# PING2_PCB.net
KiCad netlist of a schematic drawn in Altium Designer
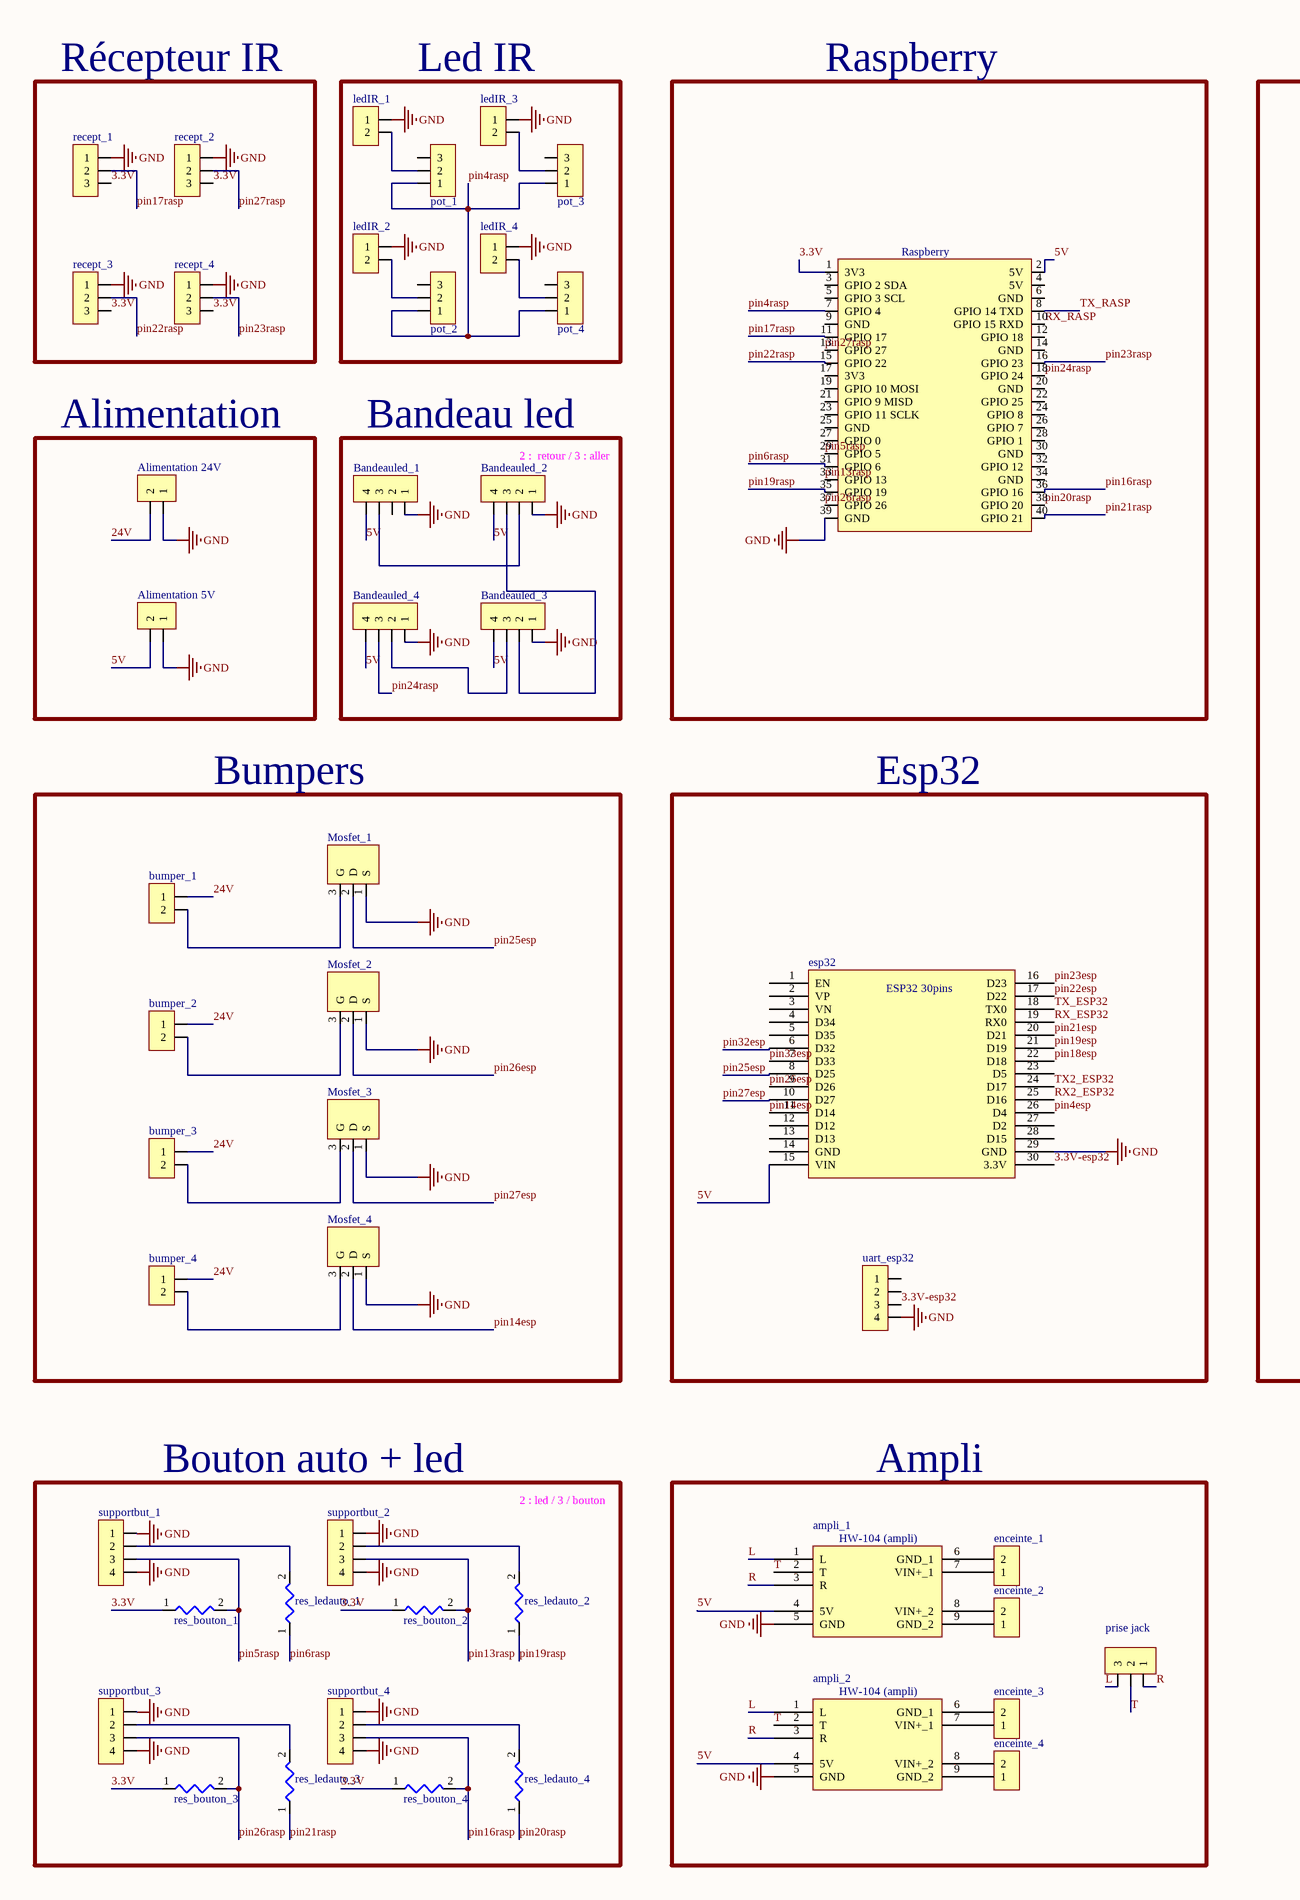
[diagram p0: PING2_PCB.SchDoc, left]
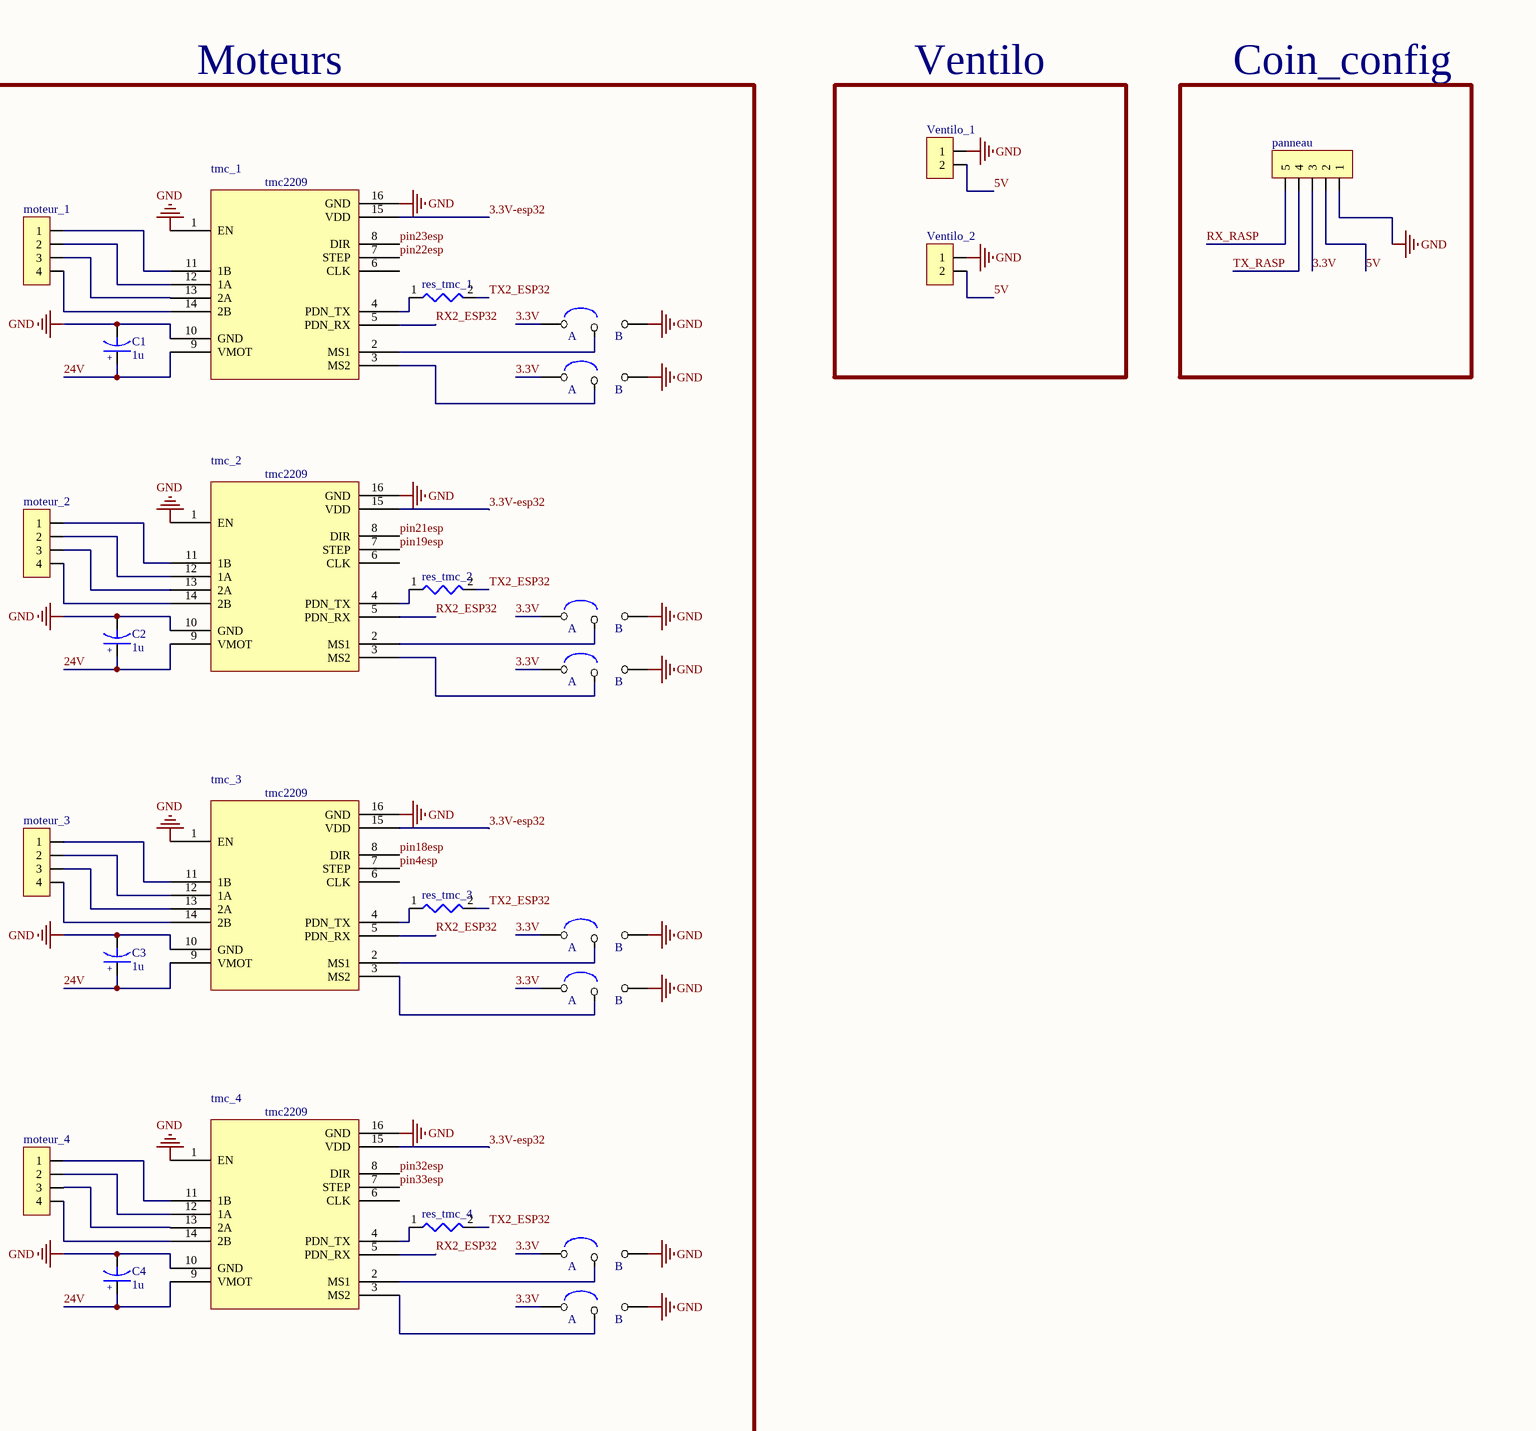
[diagram p1: PING2_PCB.SchDoc, right]

(export (version "E")
  (design (tool "Eeschema 10.0.6"))
  (components
    (comp (ref "Alimentation 5V")
      (value "Header_2")
      (footprint "Header_2")
      (libsource (lib "") (part "Header_2_2"))
    )
    (comp (ref "Alimentation 24V")
      (value "Header_2")
      (footprint "Header_2")
      (libsource (lib "") (part "Header_2_2"))
    )
    (comp (ref "ampli_1")
      (value "HW-104 (ampli)")
      (footprint "HW-104 (ampli)")
      (libsource (lib "Simon_library") (part "HW-104 (ampli)"))
    )
    (comp (ref "ampli_2")
      (value "HW-104 (ampli)")
      (footprint "HW-104 (ampli)")
      (libsource (lib "Simon_library") (part "HW-104 (ampli)"))
    )
    (comp (ref "Bandeauled_1")
      (value "Header_4")
      (footprint "Header_4")
      (libsource (lib "Simon_library") (part "Header_4"))
    )
    (comp (ref "Bandeauled_2")
      (value "Header_4")
      (footprint "Header_4")
      (libsource (lib "Simon_library") (part "Header_4"))
    )
    (comp (ref "Bandeauled_3")
      (value "Header_4")
      (footprint "Header_4")
      (libsource (lib "Simon_library") (part "Header_4"))
    )
    (comp (ref "Bandeauled_4")
      (value "Header_4")
      (footprint "Header_4")
      (libsource (lib "Simon_library") (part "Header_4"))
    )
    (comp (ref "bumper_1")
      (value "Header_2")
      (footprint "Header_2")
      (libsource (lib "Simon_library") (part "Header_2"))
    )
    (comp (ref "bumper_2")
      (value "Header_2")
      (footprint "Header_2")
      (libsource (lib "Simon_library") (part "Header_2"))
    )
    (comp (ref "bumper_3")
      (value "Header_2")
      (footprint "Header_2")
      (libsource (lib "Simon_library") (part "Header_2"))
    )
    (comp (ref "bumper_4")
      (value "Header_2")
      (footprint "Header_2")
      (libsource (lib "Simon_library") (part "Header_2"))
    )
    (comp (ref "C1")
      (value "1u")
      (footprint "RB.2/.4")
      (description "capacité polarisée")
      (fields (field (name "Comment") "CAP_POL"))
      (libsource (lib "ISEN_basics_19052021") (part "CAP_POL"))
    )
    (comp (ref "C2")
      (value "1u")
      (footprint "RB.2/.4")
      (description "capacité polarisée")
      (fields (field (name "Comment") "CAP_POL"))
      (libsource (lib "ISEN_basics_19052021") (part "CAP_POL"))
    )
    (comp (ref "C3")
      (value "1u")
      (footprint "RB.2/.4")
      (description "capacité polarisée")
      (fields (field (name "Comment") "CAP_POL"))
      (libsource (lib "ISEN_basics_19052021") (part "CAP_POL"))
    )
    (comp (ref "C4")
      (value "1u")
      (footprint "RB.2/.4")
      (description "capacité polarisée")
      (fields (field (name "Comment") "CAP_POL"))
      (libsource (lib "ISEN_basics_19052021") (part "CAP_POL"))
    )
    (comp (ref "enceinte_1")
      (value "Header_2")
      (footprint "Header_2")
      (libsource (lib "") (part "Header_2_1"))
    )
    (comp (ref "enceinte_2")
      (value "Header_2")
      (footprint "Header_2")
      (libsource (lib "") (part "Header_2_1"))
    )
    (comp (ref "enceinte_3")
      (value "Header_2")
      (footprint "Header_2")
      (libsource (lib "") (part "Header_2_1"))
    )
    (comp (ref "enceinte_4")
      (value "Header_2")
      (footprint "Header_2")
      (libsource (lib "") (part "Header_2_1"))
    )
    (comp (ref "esp32")
      (value "esp32-30pins")
      (footprint "esp32-30pins")
      (libsource (lib "Simon_library") (part "esp32-30pins"))
    )
    (comp (ref "JMP11")
      (value "JUMPER3")
      (footprint "JMP3-100")
      (description "cavalier 2 positions")
      (libsource (lib "ISEN_basics_19052021") (part "JUMPER3"))
    )
    (comp (ref "JMP12")
      (value "JUMPER3")
      (footprint "JMP3-100")
      (description "cavalier 2 positions")
      (libsource (lib "ISEN_basics_19052021") (part "JUMPER3"))
    )
    (comp (ref "JMP21")
      (value "JUMPER3")
      (footprint "JMP3-100")
      (description "cavalier 2 positions")
      (libsource (lib "ISEN_basics_19052021") (part "JUMPER3"))
    )
    (comp (ref "JMP22")
      (value "JUMPER3")
      (footprint "JMP3-100")
      (description "cavalier 2 positions")
      (libsource (lib "ISEN_basics_19052021") (part "JUMPER3"))
    )
    (comp (ref "JMP31")
      (value "JUMPER3")
      (footprint "JMP3-100")
      (description "cavalier 2 positions")
      (libsource (lib "ISEN_basics_19052021") (part "JUMPER3"))
    )
    (comp (ref "JMP32")
      (value "JUMPER3")
      (footprint "JMP3-100")
      (description "cavalier 2 positions")
      (libsource (lib "ISEN_basics_19052021") (part "JUMPER3"))
    )
    (comp (ref "JMP41")
      (value "JUMPER3")
      (footprint "JMP3-100")
      (description "cavalier 2 positions")
      (libsource (lib "ISEN_basics_19052021") (part "JUMPER3"))
    )
    (comp (ref "JMP42")
      (value "JUMPER3")
      (footprint "JMP3-100")
      (description "cavalier 2 positions")
      (libsource (lib "ISEN_basics_19052021") (part "JUMPER3"))
    )
    (comp (ref "ledIR_1")
      (value "Header_2")
      (footprint "Header_2")
      (libsource (lib "Simon_library") (part "Header_2"))
    )
    (comp (ref "ledIR_2")
      (value "Header_2")
      (footprint "Header_2")
      (libsource (lib "Simon_library") (part "Header_2"))
    )
    (comp (ref "ledIR_3")
      (value "Header_2")
      (footprint "Header_2")
      (libsource (lib "Simon_library") (part "Header_2"))
    )
    (comp (ref "ledIR_4")
      (value "Header_2")
      (footprint "Header_2")
      (libsource (lib "Simon_library") (part "Header_2"))
    )
    (comp (ref "Mosfet_1")
      (value "Mosfet")
      (footprint "Mosfet")
      (libsource (lib "Simon_library") (part "Mosfet"))
    )
    (comp (ref "Mosfet_2")
      (value "Mosfet")
      (footprint "Mosfet")
      (libsource (lib "Simon_library") (part "Mosfet"))
    )
    (comp (ref "Mosfet_3")
      (value "Mosfet")
      (footprint "Mosfet")
      (libsource (lib "Simon_library") (part "Mosfet"))
    )
    (comp (ref "Mosfet_4")
      (value "Mosfet")
      (footprint "Mosfet")
      (libsource (lib "Simon_library") (part "Mosfet"))
    )
    (comp (ref "moteur_1") (value "Header_4") (footprint "Header_4") (libsource (lib "") (part "Header_4_1")))
    (comp (ref "moteur_2") (value "Header_4") (footprint "Header_4") (libsource (lib "") (part "Header_4_1")))
    (comp (ref "moteur_3") (value "Header_4") (footprint "Header_4") (libsource (lib "") (part "Header_4_1")))
    (comp (ref "moteur_4") (value "Header_4") (footprint "Header_4") (libsource (lib "") (part "Header_4_1")))
    (comp (ref "panneau")
      (value "Header_5")
      (footprint "Header_5")
      (libsource (lib "Simon_library") (part "Header_5"))
    )
    (comp (ref "pot_1")
      (value "potentiometre_variable")
      (footprint "Potentiometre_variable")
      (libsource (lib "Simon_library") (part "potentiometre_variable"))
    )
    (comp (ref "pot_2")
      (value "potentiometre_variable")
      (footprint "Potentiometre_variable")
      (libsource (lib "Simon_library") (part "potentiometre_variable"))
    )
    (comp (ref "pot_3")
      (value "potentiometre_variable")
      (footprint "Potentiometre_variable")
      (libsource (lib "Simon_library") (part "potentiometre_variable"))
    )
    (comp (ref "pot_4")
      (value "potentiometre_variable")
      (footprint "Potentiometre_variable")
      (libsource (lib "Simon_library") (part "potentiometre_variable"))
    )
    (comp (ref "prise jack")
      (value "Header_3")
      (footprint "Header_3")
      (libsource (lib "") (part "Header_3_1"))
    )
    (comp (ref "Raspberry")
      (value "raspberry_3B+")
      (footprint "raspberry_3b+")
      (libsource (lib "Simon_library") (part "raspberry_3B+"))
    )
    (comp (ref "recept_1")
      (value "Header_3")
      (footprint "Header_3")
      (libsource (lib "Simon_library") (part "Header_3"))
    )
    (comp (ref "recept_2")
      (value "Header_3")
      (footprint "Header_3")
      (libsource (lib "Simon_library") (part "Header_3"))
    )
    (comp (ref "recept_3")
      (value "Header_3")
      (footprint "Header_3")
      (libsource (lib "Simon_library") (part "Header_3"))
    )
    (comp (ref "recept_4")
      (value "Header_3")
      (footprint "Header_3")
      (libsource (lib "Simon_library") (part "Header_3"))
    )
    (comp (ref "res_bouton_1")
      (value "resistance")
      (footprint "resistance")
      (libsource (lib "Simon_library") (part "resistance"))
    )
    (comp (ref "res_bouton_2")
      (value "resistance")
      (footprint "resistance")
      (libsource (lib "Simon_library") (part "resistance"))
    )
    (comp (ref "res_bouton_3")
      (value "resistance")
      (footprint "resistance")
      (libsource (lib "Simon_library") (part "resistance"))
    )
    (comp (ref "res_bouton_4")
      (value "resistance")
      (footprint "resistance")
      (libsource (lib "Simon_library") (part "resistance"))
    )
    (comp (ref "res_ledauto_1")
      (value "resistance")
      (footprint "resistance")
      (libsource (lib "Simon_library") (part "resistance"))
    )
    (comp (ref "res_ledauto_2")
      (value "resistance")
      (footprint "resistance")
      (libsource (lib "Simon_library") (part "resistance"))
    )
    (comp (ref "res_ledauto_3")
      (value "resistance")
      (footprint "resistance")
      (libsource (lib "Simon_library") (part "resistance"))
    )
    (comp (ref "res_ledauto_4")
      (value "resistance")
      (footprint "resistance")
      (libsource (lib "Simon_library") (part "resistance"))
    )
    (comp (ref "res_tmc_1")
      (value "resistance")
      (footprint "resistance")
      (libsource (lib "Simon_library") (part "resistance"))
    )
    (comp (ref "res_tmc_2")
      (value "resistance")
      (footprint "resistance")
      (libsource (lib "Simon_library") (part "resistance"))
    )
    (comp (ref "res_tmc_3")
      (value "resistance")
      (footprint "resistance")
      (libsource (lib "Simon_library") (part "resistance"))
    )
    (comp (ref "res_tmc_4")
      (value "resistance")
      (footprint "resistance")
      (libsource (lib "Simon_library") (part "resistance"))
    )
    (comp (ref "supportbut_1")
      (value "Header_4")
      (footprint "Header_4")
      (libsource (lib "") (part "Header_4_1"))
    )
    (comp (ref "supportbut_2")
      (value "Header_4")
      (footprint "Header_4")
      (libsource (lib "") (part "Header_4_1"))
    )
    (comp (ref "supportbut_3")
      (value "Header_4")
      (footprint "Header_4")
      (libsource (lib "") (part "Header_4_1"))
    )
    (comp (ref "supportbut_4")
      (value "Header_4")
      (footprint "Header_4")
      (libsource (lib "") (part "Header_4_1"))
    )
    (comp (ref "tmc_1")
      (value "tmc2209")
      (footprint "tmc2209")
      (libsource (lib "Simon_library") (part "tmc2209"))
    )
    (comp (ref "tmc_2")
      (value "tmc2209")
      (footprint "tmc2209")
      (libsource (lib "Simon_library") (part "tmc2209"))
    )
    (comp (ref "tmc_3")
      (value "tmc2209")
      (footprint "tmc2209")
      (libsource (lib "Simon_library") (part "tmc2209"))
    )
    (comp (ref "tmc_4")
      (value "tmc2209")
      (footprint "tmc2209")
      (libsource (lib "Simon_library") (part "tmc2209"))
    )
    (comp (ref "uart_esp32")
      (value "Header_4")
      (footprint "Header_4")
      (libsource (lib "") (part "Header_4_1"))
    )
    (comp (ref "Ventilo_1")
      (value "Header_2")
      (footprint "Header_2")
      (libsource (lib "Simon_library") (part "Header_2"))
    )
    (comp (ref "Ventilo_2")
      (value "Header_2")
      (footprint "Header_2")
      (libsource (lib "Simon_library") (part "Header_2"))
    )
  )
  (nets
    (net (code "1") (name "/3.3V") (class "Default")
      (node (ref "JMP11") (pin "1") (pintype "passive"))
      (node (ref "JMP12") (pin "1") (pintype "passive"))
      (node (ref "JMP21") (pin "1") (pintype "passive"))
      (node (ref "JMP22") (pin "1") (pintype "passive"))
      (node (ref "JMP31") (pin "1") (pintype "passive"))
      (node (ref "JMP32") (pin "1") (pintype "passive"))
      (node (ref "JMP41") (pin "1") (pintype "passive"))
      (node (ref "JMP42") (pin "1") (pintype "passive"))
      (node (ref "Raspberry") (pin "1") (pinfunction "3V3_1") (pintype "passive"))
      (node (ref "panneau") (pin "3") (pinfunction "3_3") (pintype "passive"))
      (node (ref "recept_1") (pin "3") (pinfunction "3_3") (pintype "passive"))
      (node (ref "recept_2") (pin "3") (pinfunction "3_3") (pintype "passive"))
      (node (ref "recept_3") (pin "3") (pinfunction "3_3") (pintype "passive"))
      (node (ref "recept_4") (pin "3") (pinfunction "3_3") (pintype "passive"))
      (node (ref "res_bouton_1") (pin "1") (pinfunction "1_1") (pintype "passive"))
      (node (ref "res_bouton_2") (pin "1") (pinfunction "1_1") (pintype "passive"))
      (node (ref "res_bouton_3") (pin "1") (pinfunction "1_1") (pintype "passive"))
      (node (ref "res_bouton_4") (pin "1") (pinfunction "1_1") (pintype "passive"))
    )
    (net (code "2") (name "/3.3V-esp32") (class "Default")
      (node (ref "esp32") (pin "30") (pinfunction "3.3V_30") (pintype "passive"))
      (node (ref "tmc_1") (pin "15") (pinfunction "VDD_15") (pintype "power_in"))
      (node (ref "tmc_2") (pin "15") (pinfunction "VDD_15") (pintype "power_in"))
      (node (ref "tmc_3") (pin "15") (pinfunction "VDD_15") (pintype "power_in"))
      (node (ref "tmc_4") (pin "15") (pinfunction "VDD_15") (pintype "power_in"))
      (node (ref "uart_esp32") (pin "3") (pinfunction "3_3") (pintype "passive"))
    )
    (net (code "3") (name "/5V") (class "Default")
      (node (ref "Alimentation 5V") (pin "2") (pinfunction "2_2") (pintype "passive"))
      (node (ref "Bandeauled_1") (pin "4") (pinfunction "4_4") (pintype "passive"))
      (node (ref "Bandeauled_2") (pin "4") (pinfunction "4_4") (pintype "passive"))
      (node (ref "Bandeauled_3") (pin "4") (pinfunction "4_4") (pintype "passive"))
      (node (ref "Bandeauled_4") (pin "4") (pinfunction "4_4") (pintype "passive"))
      (node (ref "Raspberry") (pin "2") (pinfunction "5V_2") (pintype "passive"))
      (node (ref "Ventilo_1") (pin "2") (pinfunction "2_2") (pintype "passive"))
      (node (ref "Ventilo_2") (pin "2") (pinfunction "2_2") (pintype "passive"))
      (node (ref "ampli_1") (pin "4") (pinfunction "5V_4") (pintype "passive"))
      (node (ref "ampli_2") (pin "4") (pinfunction "5V_4") (pintype "passive"))
      (node (ref "esp32") (pin "15") (pinfunction "VIN_15") (pintype "passive"))
      (node (ref "panneau") (pin "2") (pinfunction "2_2") (pintype "passive"))
    )
    (net (code "4") (name "/24V") (class "Default")
      (node (ref "Alimentation 24V") (pin "2") (pinfunction "2_2") (pintype "passive"))
      (node (ref "C1") (pin "1") (pinfunction "1_1") (pintype "passive"))
      (node (ref "C2") (pin "1") (pinfunction "1_1") (pintype "passive"))
      (node (ref "C3") (pin "1") (pinfunction "1_1") (pintype "passive"))
      (node (ref "C4") (pin "1") (pinfunction "1_1") (pintype "passive"))
      (node (ref "bumper_1") (pin "1") (pinfunction "1_1") (pintype "passive"))
      (node (ref "bumper_2") (pin "1") (pinfunction "1_1") (pintype "passive"))
      (node (ref "bumper_3") (pin "1") (pinfunction "1_1") (pintype "passive"))
      (node (ref "bumper_4") (pin "1") (pinfunction "1_1") (pintype "passive"))
      (node (ref "tmc_1") (pin "9") (pinfunction "VMOT_9") (pintype "power_in"))
      (node (ref "tmc_2") (pin "9") (pinfunction "VMOT_9") (pintype "power_in"))
      (node (ref "tmc_3") (pin "9") (pinfunction "VMOT_9") (pintype "power_in"))
      (node (ref "tmc_4") (pin "9") (pinfunction "VMOT_9") (pintype "power_in"))
    )
    (net (code "5") (name "/L") (class "Default")
      (node (ref "ampli_1") (pin "1") (pinfunction "L_1") (pintype "passive"))
      (node (ref "ampli_2") (pin "1") (pinfunction "L_1") (pintype "passive"))
      (node (ref "prise jack") (pin "3") (pinfunction "3_3") (pintype "passive"))
    )
    (net (code "6") (name "/R") (class "Default")
      (node (ref "ampli_1") (pin "3") (pinfunction "R_3") (pintype "passive"))
      (node (ref "ampli_2") (pin "3") (pinfunction "R_3") (pintype "passive"))
      (node (ref "prise jack") (pin "1") (pinfunction "1_1") (pintype "passive"))
    )
    (net (code "7") (name "/RX2_ESP32") (class "Default")
      (node (ref "esp32") (pin "25") (pinfunction "D16_25") (pintype "passive"))
      (node (ref "tmc_1") (pin "5") (pinfunction "PDN_RX_5") (pintype "passive"))
      (node (ref "tmc_2") (pin "5") (pinfunction "PDN_RX_5") (pintype "passive"))
      (node (ref "tmc_3") (pin "5") (pinfunction "PDN_RX_5") (pintype "passive"))
      (node (ref "tmc_4") (pin "5") (pinfunction "PDN_RX_5") (pintype "passive"))
    )
    (net (code "8") (name "/RX_ESP32") (class "Default")
      (node (ref "esp32") (pin "19") (pinfunction "RX0_19") (pintype "passive"))
    )
    (net (code "9") (name "/RX_RASP") (class "Default")
      (node (ref "Raspberry") (pin "10") (pinfunction "GPIO_15_RXD_10") (pintype "passive"))
      (node (ref "panneau") (pin "5") (pinfunction "5_5") (pintype "passive"))
    )
    (net (code "10") (name "/T") (class "Default")
      (node (ref "ampli_1") (pin "2") (pinfunction "T_2") (pintype "passive"))
      (node (ref "ampli_2") (pin "2") (pinfunction "T_2") (pintype "passive"))
      (node (ref "prise jack") (pin "2") (pinfunction "2_2") (pintype "passive"))
    )
    (net (code "11") (name "/TX2_ESP32") (class "Default")
      (node (ref "esp32") (pin "24") (pinfunction "D17_24") (pintype "passive"))
      (node (ref "res_tmc_1") (pin "2") (pinfunction "2_2") (pintype "passive"))
      (node (ref "res_tmc_2") (pin "2") (pinfunction "2_2") (pintype "passive"))
      (node (ref "res_tmc_3") (pin "2") (pinfunction "2_2") (pintype "passive"))
      (node (ref "res_tmc_4") (pin "2") (pinfunction "2_2") (pintype "passive"))
    )
    (net (code "12") (name "/TX_ESP32") (class "Default")
      (node (ref "esp32") (pin "18") (pinfunction "TX0_18") (pintype "passive"))
    )
    (net (code "13") (name "/TX_RASP") (class "Default")
      (node (ref "Raspberry") (pin "8") (pinfunction "GPIO_14_TXD_8") (pintype "passive"))
      (node (ref "panneau") (pin "4") (pinfunction "4_4") (pintype "passive"))
    )
    (net (code "14") (name "/pin4esp") (class "Default")
      (node (ref "esp32") (pin "26") (pinfunction "D4_26") (pintype "passive"))
      (node (ref "tmc_3") (pin "7") (pinfunction "STEP_7") (pintype "passive"))
    )
    (net (code "15") (name "/pin4rasp") (class "Default")
      (node (ref "Raspberry") (pin "7") (pinfunction "GPIO_4_7") (pintype "passive"))
      (node (ref "pot_1") (pin "1") (pinfunction "1_1") (pintype "passive"))
      (node (ref "pot_2") (pin "1") (pinfunction "1_1") (pintype "passive"))
      (node (ref "pot_3") (pin "1") (pinfunction "1_1") (pintype "passive"))
      (node (ref "pot_4") (pin "1") (pinfunction "1_1") (pintype "passive"))
    )
    (net (code "16") (name "/pin5rasp") (class "Default")
      (node (ref "Raspberry") (pin "29") (pinfunction "GPIO_5_29") (pintype "passive"))
      (node (ref "res_bouton_1") (pin "2") (pinfunction "2_2") (pintype "passive"))
      (node (ref "supportbut_1") (pin "3") (pinfunction "3_3") (pintype "passive"))
    )
    (net (code "17") (name "/pin6rasp") (class "Default")
      (node (ref "Raspberry") (pin "31") (pinfunction "GPIO_6_31") (pintype "passive"))
      (node (ref "res_ledauto_1") (pin "1") (pinfunction "1_1") (pintype "passive"))
    )
    (net (code "18") (name "/pin13rasp") (class "Default")
      (node (ref "Raspberry") (pin "33") (pinfunction "GPIO_13_33") (pintype "passive"))
      (node (ref "res_bouton_2") (pin "2") (pinfunction "2_2") (pintype "passive"))
      (node (ref "supportbut_2") (pin "3") (pinfunction "3_3") (pintype "passive"))
    )
    (net (code "19") (name "/pin14esp") (class "Default")
      (node (ref "Mosfet_4") (pin "2") (pinfunction "D_2") (pintype "passive"))
      (node (ref "esp32") (pin "11") (pinfunction "D14_11") (pintype "passive"))
    )
    (net (code "20") (name "/pin16rasp") (class "Default")
      (node (ref "Raspberry") (pin "36") (pinfunction "GPIO_16_36") (pintype "passive"))
      (node (ref "res_bouton_4") (pin "2") (pinfunction "2_2") (pintype "passive"))
      (node (ref "supportbut_4") (pin "3") (pinfunction "3_3") (pintype "passive"))
    )
    (net (code "21") (name "/pin17rasp") (class "Default")
      (node (ref "Raspberry") (pin "11") (pinfunction "GPIO_17_11") (pintype "passive"))
      (node (ref "recept_1") (pin "2") (pinfunction "2_2") (pintype "passive"))
    )
    (net (code "22") (name "/pin18esp") (class "Default")
      (node (ref "esp32") (pin "22") (pinfunction "D18_22") (pintype "passive"))
      (node (ref "tmc_3") (pin "8") (pinfunction "DIR_8") (pintype "passive"))
    )
    (net (code "23") (name "/pin19esp") (class "Default")
      (node (ref "esp32") (pin "21") (pinfunction "D19_21") (pintype "passive"))
      (node (ref "tmc_2") (pin "7") (pinfunction "STEP_7") (pintype "passive"))
    )
    (net (code "24") (name "/pin19rasp") (class "Default")
      (node (ref "Raspberry") (pin "35") (pinfunction "GPIO_19_35") (pintype "passive"))
      (node (ref "res_ledauto_2") (pin "1") (pinfunction "1_1") (pintype "passive"))
    )
    (net (code "25") (name "/pin20rasp") (class "Default")
      (node (ref "Raspberry") (pin "38") (pinfunction "GPIO_20_38") (pintype "passive"))
      (node (ref "res_ledauto_4") (pin "1") (pinfunction "1_1") (pintype "passive"))
    )
    (net (code "26") (name "/pin21esp") (class "Default")
      (node (ref "esp32") (pin "20") (pinfunction "D21_20") (pintype "passive"))
      (node (ref "tmc_2") (pin "8") (pinfunction "DIR_8") (pintype "passive"))
    )
    (net (code "27") (name "/pin21rasp") (class "Default")
      (node (ref "Raspberry") (pin "40") (pinfunction "GPIO_21_40") (pintype "passive"))
      (node (ref "res_ledauto_3") (pin "1") (pinfunction "1_1") (pintype "passive"))
    )
    (net (code "28") (name "/pin22esp") (class "Default")
      (node (ref "esp32") (pin "17") (pinfunction "D22_17") (pintype "passive"))
      (node (ref "tmc_1") (pin "7") (pinfunction "STEP_7") (pintype "passive"))
    )
    (net (code "29") (name "/pin22rasp") (class "Default")
      (node (ref "Raspberry") (pin "15") (pinfunction "GPIO_22_15") (pintype "passive"))
      (node (ref "recept_3") (pin "2") (pinfunction "2_2") (pintype "passive"))
    )
    (net (code "30") (name "/pin23esp") (class "Default")
      (node (ref "esp32") (pin "16") (pinfunction "D23_16") (pintype "passive"))
      (node (ref "tmc_1") (pin "8") (pinfunction "DIR_8") (pintype "passive"))
    )
    (net (code "31") (name "/pin23rasp") (class "Default")
      (node (ref "Raspberry") (pin "16") (pinfunction "GPIO_23_16") (pintype "passive"))
      (node (ref "recept_4") (pin "2") (pinfunction "2_2") (pintype "passive"))
    )
    (net (code "32") (name "/pin24rasp") (class "Default")
      (node (ref "Bandeauled_4") (pin "3") (pinfunction "3_3") (pintype "passive"))
      (node (ref "Raspberry") (pin "18") (pinfunction "GPIO_24_18") (pintype "passive"))
    )
    (net (code "33") (name "/pin25esp") (class "Default")
      (node (ref "Mosfet_1") (pin "2") (pinfunction "D_2") (pintype "passive"))
      (node (ref "esp32") (pin "8") (pinfunction "D25_8") (pintype "passive"))
    )
    (net (code "34") (name "/pin26esp") (class "Default")
      (node (ref "Mosfet_2") (pin "2") (pinfunction "D_2") (pintype "passive"))
      (node (ref "esp32") (pin "9") (pinfunction "D26_9") (pintype "passive"))
    )
    (net (code "35") (name "/pin26rasp") (class "Default")
      (node (ref "Raspberry") (pin "37") (pinfunction "GPIO_26_37") (pintype "passive"))
      (node (ref "res_bouton_3") (pin "2") (pinfunction "2_2") (pintype "passive"))
      (node (ref "supportbut_3") (pin "3") (pinfunction "3_3") (pintype "passive"))
    )
    (net (code "36") (name "/pin27esp") (class "Default")
      (node (ref "Mosfet_3") (pin "2") (pinfunction "D_2") (pintype "passive"))
      (node (ref "esp32") (pin "10") (pinfunction "D27_10") (pintype "passive"))
    )
    (net (code "37") (name "/pin27rasp") (class "Default")
      (node (ref "Raspberry") (pin "13") (pinfunction "GPIO_27_13") (pintype "passive"))
      (node (ref "recept_2") (pin "2") (pinfunction "2_2") (pintype "passive"))
    )
    (net (code "38") (name "/pin32esp") (class "Default")
      (node (ref "esp32") (pin "6") (pinfunction "D32_6") (pintype "passive"))
      (node (ref "tmc_4") (pin "8") (pinfunction "DIR_8") (pintype "passive"))
    )
    (net (code "39") (name "/pin33esp") (class "Default")
      (node (ref "esp32") (pin "7") (pinfunction "D33_7") (pintype "passive"))
      (node (ref "tmc_4") (pin "7") (pinfunction "STEP_7") (pintype "passive"))
    )
    (net (code "40") (name "GND") (class "Default")
      (node (ref "Alimentation 24V") (pin "1") (pinfunction "1_1") (pintype "passive"))
      (node (ref "Alimentation 5V") (pin "1") (pinfunction "1_1") (pintype "passive"))
      (node (ref "Bandeauled_1") (pin "1") (pinfunction "1_1") (pintype "passive"))
      (node (ref "Bandeauled_2") (pin "1") (pinfunction "1_1") (pintype "passive"))
      (node (ref "Bandeauled_3") (pin "1") (pinfunction "1_1") (pintype "passive"))
      (node (ref "Bandeauled_4") (pin "1") (pinfunction "1_1") (pintype "passive"))
      (node (ref "C1") (pin "2") (pinfunction "2_2") (pintype "passive"))
      (node (ref "C2") (pin "2") (pinfunction "2_2") (pintype "passive"))
      (node (ref "C3") (pin "2") (pinfunction "2_2") (pintype "passive"))
      (node (ref "C4") (pin "2") (pinfunction "2_2") (pintype "passive"))
      (node (ref "JMP11") (pin "2") (pintype "passive"))
      (node (ref "JMP12") (pin "2") (pintype "passive"))
      (node (ref "JMP21") (pin "2") (pintype "passive"))
      (node (ref "JMP22") (pin "2") (pintype "passive"))
      (node (ref "JMP31") (pin "2") (pintype "passive"))
      (node (ref "JMP32") (pin "2") (pintype "passive"))
      (node (ref "JMP41") (pin "2") (pintype "passive"))
      (node (ref "JMP42") (pin "2") (pintype "passive"))
      (node (ref "Mosfet_1") (pin "1") (pinfunction "S_1") (pintype "passive"))
      (node (ref "Mosfet_2") (pin "1") (pinfunction "S_1") (pintype "passive"))
      (node (ref "Mosfet_3") (pin "1") (pinfunction "S_1") (pintype "passive"))
      (node (ref "Mosfet_4") (pin "1") (pinfunction "S_1") (pintype "passive"))
      (node (ref "Raspberry") (pin "39") (pinfunction "GND_39") (pintype "passive"))
      (node (ref "Ventilo_1") (pin "1") (pinfunction "1_1") (pintype "passive"))
      (node (ref "Ventilo_2") (pin "1") (pinfunction "1_1") (pintype "passive"))
      (node (ref "ampli_1") (pin "5") (pinfunction "GND_5") (pintype "passive"))
      (node (ref "ampli_2") (pin "5") (pinfunction "GND_5") (pintype "passive"))
      (node (ref "esp32") (pin "29") (pinfunction "GND_29") (pintype "passive"))
      (node (ref "ledIR_1") (pin "1") (pinfunction "1_1") (pintype "passive"))
      (node (ref "ledIR_2") (pin "1") (pinfunction "1_1") (pintype "passive"))
      (node (ref "ledIR_3") (pin "1") (pinfunction "1_1") (pintype "passive"))
      (node (ref "ledIR_4") (pin "1") (pinfunction "1_1") (pintype "passive"))
      (node (ref "panneau") (pin "1") (pinfunction "1_1") (pintype "passive"))
      (node (ref "recept_1") (pin "1") (pinfunction "1_1") (pintype "passive"))
      (node (ref "recept_2") (pin "1") (pinfunction "1_1") (pintype "passive"))
      (node (ref "recept_3") (pin "1") (pinfunction "1_1") (pintype "passive"))
      (node (ref "recept_4") (pin "1") (pinfunction "1_1") (pintype "passive"))
      (node (ref "supportbut_1") (pin "1") (pinfunction "1_1") (pintype "passive"))
      (node (ref "supportbut_1") (pin "4") (pinfunction "4_4") (pintype "passive"))
      (node (ref "supportbut_2") (pin "1") (pinfunction "1_1") (pintype "passive"))
      (node (ref "supportbut_2") (pin "4") (pinfunction "4_4") (pintype "passive"))
      (node (ref "supportbut_3") (pin "1") (pinfunction "1_1") (pintype "passive"))
      (node (ref "supportbut_3") (pin "4") (pinfunction "4_4") (pintype "passive"))
      (node (ref "supportbut_4") (pin "1") (pinfunction "1_1") (pintype "passive"))
      (node (ref "supportbut_4") (pin "4") (pinfunction "4_4") (pintype "passive"))
      (node (ref "tmc_1") (pin "1") (pinfunction "EN_1") (pintype "passive"))
      (node (ref "tmc_1") (pin "10") (pinfunction "GND_10") (pintype "power_in"))
      (node (ref "tmc_1") (pin "16") (pinfunction "GND_16") (pintype "power_in"))
      (node (ref "tmc_2") (pin "1") (pinfunction "EN_1") (pintype "passive"))
      (node (ref "tmc_2") (pin "10") (pinfunction "GND_10") (pintype "power_in"))
      (node (ref "tmc_2") (pin "16") (pinfunction "GND_16") (pintype "power_in"))
      (node (ref "tmc_3") (pin "1") (pinfunction "EN_1") (pintype "passive"))
      (node (ref "tmc_3") (pin "10") (pinfunction "GND_10") (pintype "power_in"))
      (node (ref "tmc_3") (pin "16") (pinfunction "GND_16") (pintype "power_in"))
      (node (ref "tmc_4") (pin "1") (pinfunction "EN_1") (pintype "passive"))
      (node (ref "tmc_4") (pin "10") (pinfunction "GND_10") (pintype "power_in"))
      (node (ref "tmc_4") (pin "16") (pinfunction "GND_16") (pintype "power_in"))
      (node (ref "uart_esp32") (pin "4") (pinfunction "4_4") (pintype "passive"))
    )
    (net (code "41") (name "Net-(Bandeauled_1-Pad3)") (class "Default")
      (node (ref "Bandeauled_1") (pin "3") (pinfunction "3_3") (pintype "passive"))
      (node (ref "Bandeauled_2") (pin "2") (pinfunction "2_2") (pintype "passive"))
    )
    (net (code "42") (name "Net-(Bandeauled_2-Pad3)") (class "Default")
      (node (ref "Bandeauled_2") (pin "3") (pinfunction "3_3") (pintype "passive"))
      (node (ref "Bandeauled_3") (pin "2") (pinfunction "2_2") (pintype "passive"))
    )
    (net (code "43") (name "Net-(Bandeauled_3-Pad3)") (class "Default")
      (node (ref "Bandeauled_3") (pin "3") (pinfunction "3_3") (pintype "passive"))
      (node (ref "Bandeauled_4") (pin "2") (pinfunction "2_2") (pintype "passive"))
    )
    (net (code "44") (name "Net-(Mosfet_1-G)") (class "Default")
      (node (ref "Mosfet_1") (pin "3") (pinfunction "G_3") (pintype "passive"))
      (node (ref "bumper_1") (pin "2") (pinfunction "2_2") (pintype "passive"))
    )
    (net (code "45") (name "Net-(Mosfet_2-G)") (class "Default")
      (node (ref "Mosfet_2") (pin "3") (pinfunction "G_3") (pintype "passive"))
      (node (ref "bumper_2") (pin "2") (pinfunction "2_2") (pintype "passive"))
    )
    (net (code "46") (name "Net-(Mosfet_3-G)") (class "Default")
      (node (ref "Mosfet_3") (pin "3") (pinfunction "G_3") (pintype "passive"))
      (node (ref "bumper_3") (pin "2") (pinfunction "2_2") (pintype "passive"))
    )
    (net (code "47") (name "Net-(Mosfet_4-G)") (class "Default")
      (node (ref "Mosfet_4") (pin "3") (pinfunction "G_3") (pintype "passive"))
      (node (ref "bumper_4") (pin "2") (pinfunction "2_2") (pintype "passive"))
    )
    (net (code "48") (name "Net-(ampli_1-GND_1)") (class "Default")
      (node (ref "ampli_1") (pin "6") (pinfunction "GND_1_6") (pintype "passive"))
      (node (ref "enceinte_1") (pin "2") (pinfunction "2_2") (pintype "passive"))
    )
    (net (code "49") (name "Net-(ampli_1-GND_2)") (class "Default")
      (node (ref "ampli_1") (pin "9") (pinfunction "GND_2_9") (pintype "passive"))
      (node (ref "enceinte_2") (pin "1") (pinfunction "1_1") (pintype "passive"))
    )
    (net (code "50") (name "Net-(ampli_1-VIN+_1)") (class "Default")
      (node (ref "ampli_1") (pin "7") (pinfunction "VIN+_1_7") (pintype "passive"))
      (node (ref "enceinte_1") (pin "1") (pinfunction "1_1") (pintype "passive"))
    )
    (net (code "51") (name "Net-(ampli_1-VIN+_2)") (class "Default")
      (node (ref "ampli_1") (pin "8") (pinfunction "VIN+_2_8") (pintype "passive"))
      (node (ref "enceinte_2") (pin "2") (pinfunction "2_2") (pintype "passive"))
    )
    (net (code "52") (name "Net-(ampli_2-GND_1)") (class "Default")
      (node (ref "ampli_2") (pin "6") (pinfunction "GND_1_6") (pintype "passive"))
      (node (ref "enceinte_3") (pin "2") (pinfunction "2_2") (pintype "passive"))
    )
    (net (code "53") (name "Net-(ampli_2-GND_2)") (class "Default")
      (node (ref "ampli_2") (pin "9") (pinfunction "GND_2_9") (pintype "passive"))
      (node (ref "enceinte_4") (pin "1") (pinfunction "1_1") (pintype "passive"))
    )
    (net (code "54") (name "Net-(ampli_2-VIN+_1)") (class "Default")
      (node (ref "ampli_2") (pin "7") (pinfunction "VIN+_1_7") (pintype "passive"))
      (node (ref "enceinte_3") (pin "1") (pinfunction "1_1") (pintype "passive"))
    )
    (net (code "55") (name "Net-(ampli_2-VIN+_2)") (class "Default")
      (node (ref "ampli_2") (pin "8") (pinfunction "VIN+_2_8") (pintype "passive"))
      (node (ref "enceinte_4") (pin "2") (pinfunction "2_2") (pintype "passive"))
    )
    (net (code "56") (name "Net-(ledIR_1-Pad2)") (class "Default")
      (node (ref "ledIR_1") (pin "2") (pinfunction "2_2") (pintype "passive"))
      (node (ref "pot_1") (pin "2") (pinfunction "2_2") (pintype "passive"))
    )
    (net (code "57") (name "Net-(ledIR_2-Pad2)") (class "Default")
      (node (ref "ledIR_2") (pin "2") (pinfunction "2_2") (pintype "passive"))
      (node (ref "pot_2") (pin "2") (pinfunction "2_2") (pintype "passive"))
    )
    (net (code "58") (name "Net-(ledIR_3-Pad2)") (class "Default")
      (node (ref "ledIR_3") (pin "2") (pinfunction "2_2") (pintype "passive"))
      (node (ref "pot_3") (pin "2") (pinfunction "2_2") (pintype "passive"))
    )
    (net (code "59") (name "Net-(ledIR_4-Pad2)") (class "Default")
      (node (ref "ledIR_4") (pin "2") (pinfunction "2_2") (pintype "passive"))
      (node (ref "pot_4") (pin "2") (pinfunction "2_2") (pintype "passive"))
    )
    (net (code "60") (name "Net-(res_ledauto_1-Pad2)") (class "Default")
      (node (ref "res_ledauto_1") (pin "2") (pinfunction "2_2") (pintype "passive"))
      (node (ref "supportbut_1") (pin "2") (pinfunction "2_2") (pintype "passive"))
    )
    (net (code "61") (name "Net-(res_ledauto_2-Pad2)") (class "Default")
      (node (ref "res_ledauto_2") (pin "2") (pinfunction "2_2") (pintype "passive"))
      (node (ref "supportbut_2") (pin "2") (pinfunction "2_2") (pintype "passive"))
    )
    (net (code "62") (name "Net-(res_ledauto_3-Pad2)") (class "Default")
      (node (ref "res_ledauto_3") (pin "2") (pinfunction "2_2") (pintype "passive"))
      (node (ref "supportbut_3") (pin "2") (pinfunction "2_2") (pintype "passive"))
    )
    (net (code "63") (name "Net-(res_ledauto_4-Pad2)") (class "Default")
      (node (ref "res_ledauto_4") (pin "2") (pinfunction "2_2") (pintype "passive"))
      (node (ref "supportbut_4") (pin "2") (pinfunction "2_2") (pintype "passive"))
    )
    (net (code "64") (name "Net-(tmc_1-1A)") (class "Default")
      (node (ref "moteur_1") (pin "2") (pinfunction "2_2") (pintype "passive"))
      (node (ref "tmc_1") (pin "12") (pinfunction "1A_12") (pintype "passive"))
    )
    (net (code "65") (name "Net-(tmc_1-1B)") (class "Default")
      (node (ref "moteur_1") (pin "1") (pinfunction "1_1") (pintype "passive"))
      (node (ref "tmc_1") (pin "11") (pinfunction "1B_11") (pintype "passive"))
    )
    (net (code "66") (name "Net-(tmc_1-2A)") (class "Default")
      (node (ref "moteur_1") (pin "3") (pinfunction "3_3") (pintype "passive"))
      (node (ref "tmc_1") (pin "13") (pinfunction "2A_13") (pintype "passive"))
    )
    (net (code "67") (name "Net-(tmc_1-2B)") (class "Default")
      (node (ref "moteur_1") (pin "4") (pinfunction "4_4") (pintype "passive"))
      (node (ref "tmc_1") (pin "14") (pinfunction "2B_14") (pintype "passive"))
    )
    (net (code "68") (name "Net-(tmc_1-MS1)") (class "Default")
      (node (ref "JMP11") (pin "3") (pintype "passive"))
      (node (ref "tmc_1") (pin "2") (pinfunction "MS1_2") (pintype "passive"))
    )
    (net (code "69") (name "Net-(tmc_1-MS2)") (class "Default")
      (node (ref "JMP12") (pin "3") (pintype "passive"))
      (node (ref "tmc_1") (pin "3") (pinfunction "MS2_3") (pintype "passive"))
    )
    (net (code "70") (name "Net-(tmc_1-PDN_TX)") (class "Default")
      (node (ref "res_tmc_1") (pin "1") (pinfunction "1_1") (pintype "passive"))
      (node (ref "tmc_1") (pin "4") (pinfunction "PDN_TX_4") (pintype "passive"))
    )
    (net (code "71") (name "Net-(tmc_2-1A)") (class "Default")
      (node (ref "moteur_2") (pin "2") (pinfunction "2_2") (pintype "passive"))
      (node (ref "tmc_2") (pin "12") (pinfunction "1A_12") (pintype "passive"))
    )
    (net (code "72") (name "Net-(tmc_2-1B)") (class "Default")
      (node (ref "moteur_2") (pin "1") (pinfunction "1_1") (pintype "passive"))
      (node (ref "tmc_2") (pin "11") (pinfunction "1B_11") (pintype "passive"))
    )
    (net (code "73") (name "Net-(tmc_2-2A)") (class "Default")
      (node (ref "moteur_2") (pin "3") (pinfunction "3_3") (pintype "passive"))
      (node (ref "tmc_2") (pin "13") (pinfunction "2A_13") (pintype "passive"))
    )
    (net (code "74") (name "Net-(tmc_2-2B)") (class "Default")
      (node (ref "moteur_2") (pin "4") (pinfunction "4_4") (pintype "passive"))
      (node (ref "tmc_2") (pin "14") (pinfunction "2B_14") (pintype "passive"))
    )
    (net (code "75") (name "Net-(tmc_2-MS1)") (class "Default")
      (node (ref "JMP21") (pin "3") (pintype "passive"))
      (node (ref "tmc_2") (pin "2") (pinfunction "MS1_2") (pintype "passive"))
    )
    (net (code "76") (name "Net-(tmc_2-MS2)") (class "Default")
      (node (ref "JMP22") (pin "3") (pintype "passive"))
      (node (ref "tmc_2") (pin "3") (pinfunction "MS2_3") (pintype "passive"))
    )
    (net (code "77") (name "Net-(tmc_2-PDN_TX)") (class "Default")
      (node (ref "res_tmc_2") (pin "1") (pinfunction "1_1") (pintype "passive"))
      (node (ref "tmc_2") (pin "4") (pinfunction "PDN_TX_4") (pintype "passive"))
    )
    (net (code "78") (name "Net-(tmc_3-1A)") (class "Default")
      (node (ref "moteur_3") (pin "2") (pinfunction "2_2") (pintype "passive"))
      (node (ref "tmc_3") (pin "12") (pinfunction "1A_12") (pintype "passive"))
    )
    (net (code "79") (name "Net-(tmc_3-1B)") (class "Default")
      (node (ref "moteur_3") (pin "1") (pinfunction "1_1") (pintype "passive"))
      (node (ref "tmc_3") (pin "11") (pinfunction "1B_11") (pintype "passive"))
    )
    (net (code "80") (name "Net-(tmc_3-2A)") (class "Default")
      (node (ref "moteur_3") (pin "3") (pinfunction "3_3") (pintype "passive"))
      (node (ref "tmc_3") (pin "13") (pinfunction "2A_13") (pintype "passive"))
    )
    (net (code "81") (name "Net-(tmc_3-2B)") (class "Default")
      (node (ref "moteur_3") (pin "4") (pinfunction "4_4") (pintype "passive"))
      (node (ref "tmc_3") (pin "14") (pinfunction "2B_14") (pintype "passive"))
    )
    (net (code "82") (name "Net-(tmc_3-MS1)") (class "Default")
      (node (ref "JMP31") (pin "3") (pintype "passive"))
      (node (ref "tmc_3") (pin "2") (pinfunction "MS1_2") (pintype "passive"))
    )
    (net (code "83") (name "Net-(tmc_3-MS2)") (class "Default")
      (node (ref "JMP32") (pin "3") (pintype "passive"))
      (node (ref "tmc_3") (pin "3") (pinfunction "MS2_3") (pintype "passive"))
    )
    (net (code "84") (name "Net-(tmc_3-PDN_TX)") (class "Default")
      (node (ref "res_tmc_3") (pin "1") (pinfunction "1_1") (pintype "passive"))
      (node (ref "tmc_3") (pin "4") (pinfunction "PDN_TX_4") (pintype "passive"))
    )
    (net (code "85") (name "Net-(tmc_4-1A)") (class "Default")
      (node (ref "moteur_4") (pin "2") (pinfunction "2_2") (pintype "passive"))
      (node (ref "tmc_4") (pin "12") (pinfunction "1A_12") (pintype "passive"))
    )
    (net (code "86") (name "Net-(tmc_4-1B)") (class "Default")
      (node (ref "moteur_4") (pin "1") (pinfunction "1_1") (pintype "passive"))
      (node (ref "tmc_4") (pin "11") (pinfunction "1B_11") (pintype "passive"))
    )
    (net (code "87") (name "Net-(tmc_4-2A)") (class "Default")
      (node (ref "moteur_4") (pin "3") (pinfunction "3_3") (pintype "passive"))
      (node (ref "tmc_4") (pin "13") (pinfunction "2A_13") (pintype "passive"))
    )
    (net (code "88") (name "Net-(tmc_4-2B)") (class "Default")
      (node (ref "moteur_4") (pin "4") (pinfunction "4_4") (pintype "passive"))
      (node (ref "tmc_4") (pin "14") (pinfunction "2B_14") (pintype "passive"))
    )
    (net (code "89") (name "Net-(tmc_4-MS1)") (class "Default")
      (node (ref "JMP41") (pin "3") (pintype "passive"))
      (node (ref "tmc_4") (pin "2") (pinfunction "MS1_2") (pintype "passive"))
    )
    (net (code "90") (name "Net-(tmc_4-MS2)") (class "Default")
      (node (ref "JMP42") (pin "3") (pintype "passive"))
      (node (ref "tmc_4") (pin "3") (pinfunction "MS2_3") (pintype "passive"))
    )
    (net (code "91") (name "Net-(tmc_4-PDN_TX)") (class "Default")
      (node (ref "res_tmc_4") (pin "1") (pinfunction "1_1") (pintype "passive"))
      (node (ref "tmc_4") (pin "4") (pinfunction "PDN_TX_4") (pintype "passive"))
    )
    (net (code "92") (name "unconnected-(Bandeauled_1-Pad2)") (class "Default")
      (node (ref "Bandeauled_1") (pin "2") (pinfunction "2_2") (pintype "passive"))
    )
    (net (code "93") (name "unconnected-(Raspberry-3V3-Pad17)") (class "Default")
      (node (ref "Raspberry") (pin "17") (pinfunction "3V3_17") (pintype "passive"))
    )
    (net (code "94") (name "unconnected-(Raspberry-5V-Pad4)") (class "Default")
      (node (ref "Raspberry") (pin "4") (pinfunction "5V_4") (pintype "passive"))
    )
    (net (code "95") (name "unconnected-(Raspberry-GND-Pad6)") (class "Default")
      (node (ref "Raspberry") (pin "6") (pinfunction "GND_6") (pintype "passive"))
    )
    (net (code "96") (name "unconnected-(Raspberry-GND-Pad9)") (class "Default")
      (node (ref "Raspberry") (pin "9") (pinfunction "GND_9") (pintype "passive"))
    )
    (net (code "97") (name "unconnected-(Raspberry-GND-Pad14)") (class "Default")
      (node (ref "Raspberry") (pin "14") (pinfunction "GND_14") (pintype "passive"))
    )
    (net (code "98") (name "unconnected-(Raspberry-GND-Pad20)") (class "Default")
      (node (ref "Raspberry") (pin "20") (pinfunction "GND_20") (pintype "passive"))
    )
    (net (code "99") (name "unconnected-(Raspberry-GND-Pad25)") (class "Default")
      (node (ref "Raspberry") (pin "25") (pinfunction "GND_25") (pintype "passive"))
    )
    (net (code "100") (name "unconnected-(Raspberry-GND-Pad30)") (class "Default")
      (node (ref "Raspberry") (pin "30") (pinfunction "GND_30") (pintype "passive"))
    )
    (net (code "101") (name "unconnected-(Raspberry-GND-Pad34)") (class "Default")
      (node (ref "Raspberry") (pin "34") (pinfunction "GND_34") (pintype "passive"))
    )
    (net (code "102") (name "unconnected-(Raspberry-GPIO_0-Pad27)") (class "Default")
      (node (ref "Raspberry") (pin "27") (pinfunction "GPIO_0_27") (pintype "passive"))
    )
    (net (code "103") (name "unconnected-(Raspberry-GPIO_1-Pad28)") (class "Default")
      (node (ref "Raspberry") (pin "28") (pinfunction "GPIO_1_28") (pintype "passive"))
    )
    (net (code "104") (name "unconnected-(Raspberry-GPIO_2_SDA-Pad3)") (class "Default")
      (node (ref "Raspberry") (pin "3") (pinfunction "GPIO_2_SDA_3") (pintype "passive"))
    )
    (net (code "105") (name "unconnected-(Raspberry-GPIO_3_SCL-Pad5)") (class "Default")
      (node (ref "Raspberry") (pin "5") (pinfunction "GPIO_3_SCL_5") (pintype "passive"))
    )
    (net (code "106") (name "unconnected-(Raspberry-GPIO_7-Pad26)") (class "Default")
      (node (ref "Raspberry") (pin "26") (pinfunction "GPIO_7_26") (pintype "passive"))
    )
    (net (code "107") (name "unconnected-(Raspberry-GPIO_8-Pad24)") (class "Default")
      (node (ref "Raspberry") (pin "24") (pinfunction "GPIO_8_24") (pintype "passive"))
    )
    (net (code "108") (name "unconnected-(Raspberry-GPIO_9_MISD-Pad21)") (class "Default")
      (node (ref "Raspberry") (pin "21") (pinfunction "GPIO_9_MISD_21") (pintype "passive"))
    )
    (net (code "109") (name "unconnected-(Raspberry-GPIO_10_MOSI-Pad19)") (class "Default")
      (node (ref "Raspberry") (pin "19") (pinfunction "GPIO_10_MOSI_19") (pintype "passive"))
    )
    (net (code "110") (name "unconnected-(Raspberry-GPIO_11_SCLK-Pad23)") (class "Default")
      (node (ref "Raspberry") (pin "23") (pinfunction "GPIO_11_SCLK_23") (pintype "passive"))
    )
    (net (code "111") (name "unconnected-(Raspberry-GPIO_12-Pad32)") (class "Default")
      (node (ref "Raspberry") (pin "32") (pinfunction "GPIO_12_32") (pintype "passive"))
    )
    (net (code "112") (name "unconnected-(Raspberry-GPIO_18-Pad12)") (class "Default")
      (node (ref "Raspberry") (pin "12") (pinfunction "GPIO_18_12") (pintype "passive"))
    )
    (net (code "113") (name "unconnected-(Raspberry-GPIO_25-Pad22)") (class "Default")
      (node (ref "Raspberry") (pin "22") (pinfunction "GPIO_25_22") (pintype "passive"))
    )
    (net (code "114") (name "unconnected-(esp32-D2-Pad27)") (class "Default")
      (node (ref "esp32") (pin "27") (pinfunction "D2_27") (pintype "passive"))
    )
    (net (code "115") (name "unconnected-(esp32-D5-Pad23)") (class "Default")
      (node (ref "esp32") (pin "23") (pinfunction "D5_23") (pintype "passive"))
    )
    (net (code "116") (name "unconnected-(esp32-D12-Pad12)") (class "Default")
      (node (ref "esp32") (pin "12") (pinfunction "D12_12") (pintype "passive"))
    )
    (net (code "117") (name "unconnected-(esp32-D13-Pad13)") (class "Default")
      (node (ref "esp32") (pin "13") (pinfunction "D13_13") (pintype "passive"))
    )
    (net (code "118") (name "unconnected-(esp32-D15-Pad28)") (class "Default")
      (node (ref "esp32") (pin "28") (pinfunction "D15_28") (pintype "passive"))
    )
    (net (code "119") (name "unconnected-(esp32-D34-Pad4)") (class "Default")
      (node (ref "esp32") (pin "4") (pinfunction "D34_4") (pintype "passive"))
    )
    (net (code "120") (name "unconnected-(esp32-D35-Pad5)") (class "Default")
      (node (ref "esp32") (pin "5") (pinfunction "D35_5") (pintype "passive"))
    )
    (net (code "121") (name "unconnected-(esp32-EN-Pad1)") (class "Default")
      (node (ref "esp32") (pin "1") (pinfunction "EN_1") (pintype "passive"))
    )
    (net (code "122") (name "unconnected-(esp32-GND-Pad14)") (class "Default")
      (node (ref "esp32") (pin "14") (pinfunction "GND_14") (pintype "passive"))
    )
    (net (code "123") (name "unconnected-(esp32-VN-Pad3)") (class "Default")
      (node (ref "esp32") (pin "3") (pinfunction "VN_3") (pintype "passive"))
    )
    (net (code "124") (name "unconnected-(esp32-VP-Pad2)") (class "Default")
      (node (ref "esp32") (pin "2") (pinfunction "VP_2") (pintype "passive"))
    )
    (net (code "125") (name "unconnected-(pot_1-Pad3)") (class "Default")
      (node (ref "pot_1") (pin "3") (pinfunction "3_3") (pintype "passive"))
    )
    (net (code "126") (name "unconnected-(pot_2-Pad3)") (class "Default")
      (node (ref "pot_2") (pin "3") (pinfunction "3_3") (pintype "passive"))
    )
    (net (code "127") (name "unconnected-(pot_3-Pad3)") (class "Default")
      (node (ref "pot_3") (pin "3") (pinfunction "3_3") (pintype "passive"))
    )
    (net (code "128") (name "unconnected-(pot_4-Pad3)") (class "Default")
      (node (ref "pot_4") (pin "3") (pinfunction "3_3") (pintype "passive"))
    )
    (net (code "129") (name "unconnected-(tmc_1-CLK-Pad6)") (class "Default")
      (node (ref "tmc_1") (pin "6") (pinfunction "CLK_6") (pintype "passive"))
    )
    (net (code "130") (name "unconnected-(tmc_2-CLK-Pad6)") (class "Default")
      (node (ref "tmc_2") (pin "6") (pinfunction "CLK_6") (pintype "passive"))
    )
    (net (code "131") (name "unconnected-(tmc_3-CLK-Pad6)") (class "Default")
      (node (ref "tmc_3") (pin "6") (pinfunction "CLK_6") (pintype "passive"))
    )
    (net (code "132") (name "unconnected-(tmc_4-CLK-Pad6)") (class "Default")
      (node (ref "tmc_4") (pin "6") (pinfunction "CLK_6") (pintype "passive"))
    )
    (net (code "133") (name "unconnected-(uart_esp32-Pad1)") (class "Default")
      (node (ref "uart_esp32") (pin "1") (pinfunction "1_1") (pintype "passive"))
    )
    (net (code "134") (name "unconnected-(uart_esp32-Pad2)") (class "Default")
      (node (ref "uart_esp32") (pin "2") (pinfunction "2_2") (pintype "passive"))
    )
  )
)
